# OBD-UART-ng.net
KiCad netlist of a schematic drawn in EAGLE
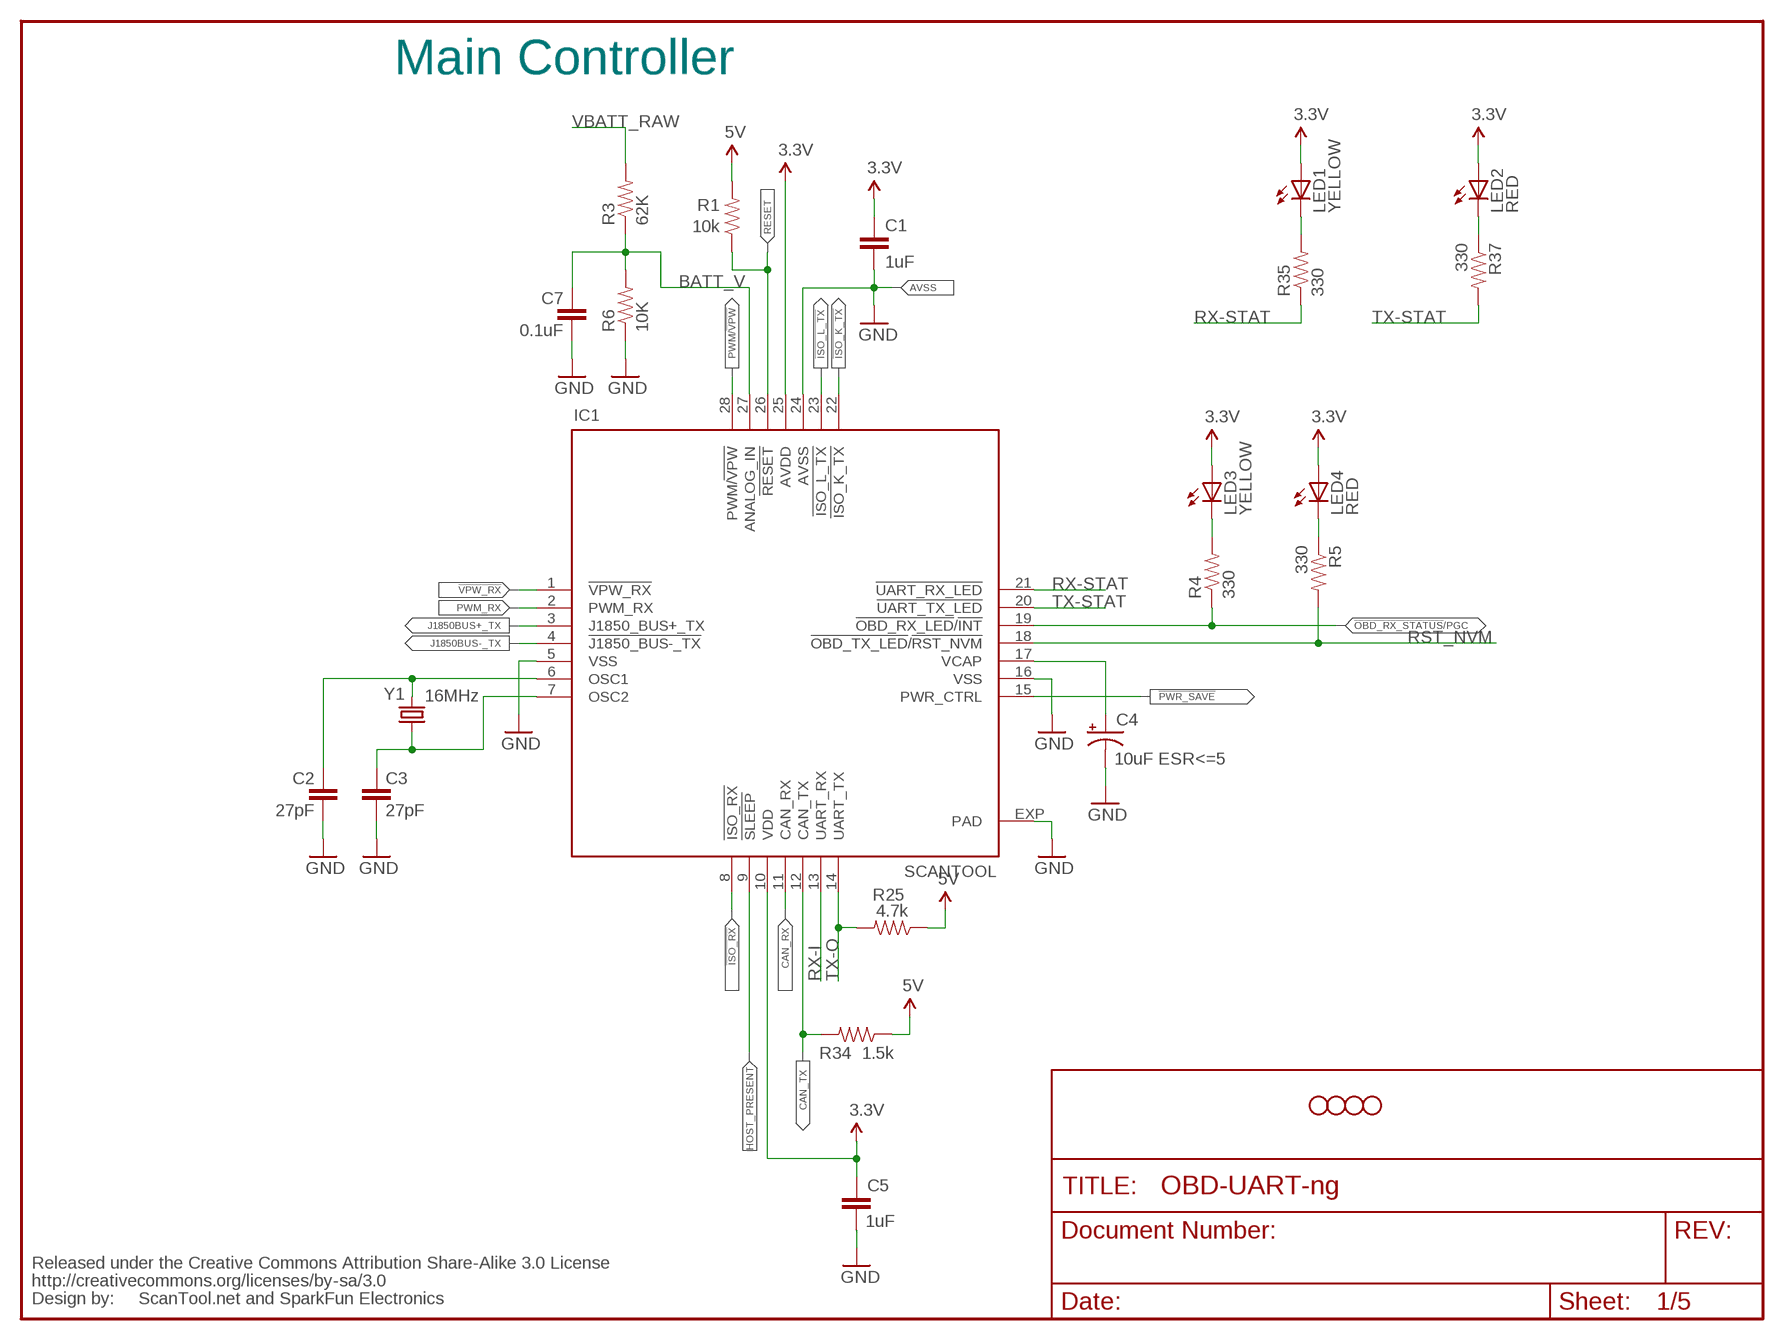
[diagram p0: schematic, sheet 1]
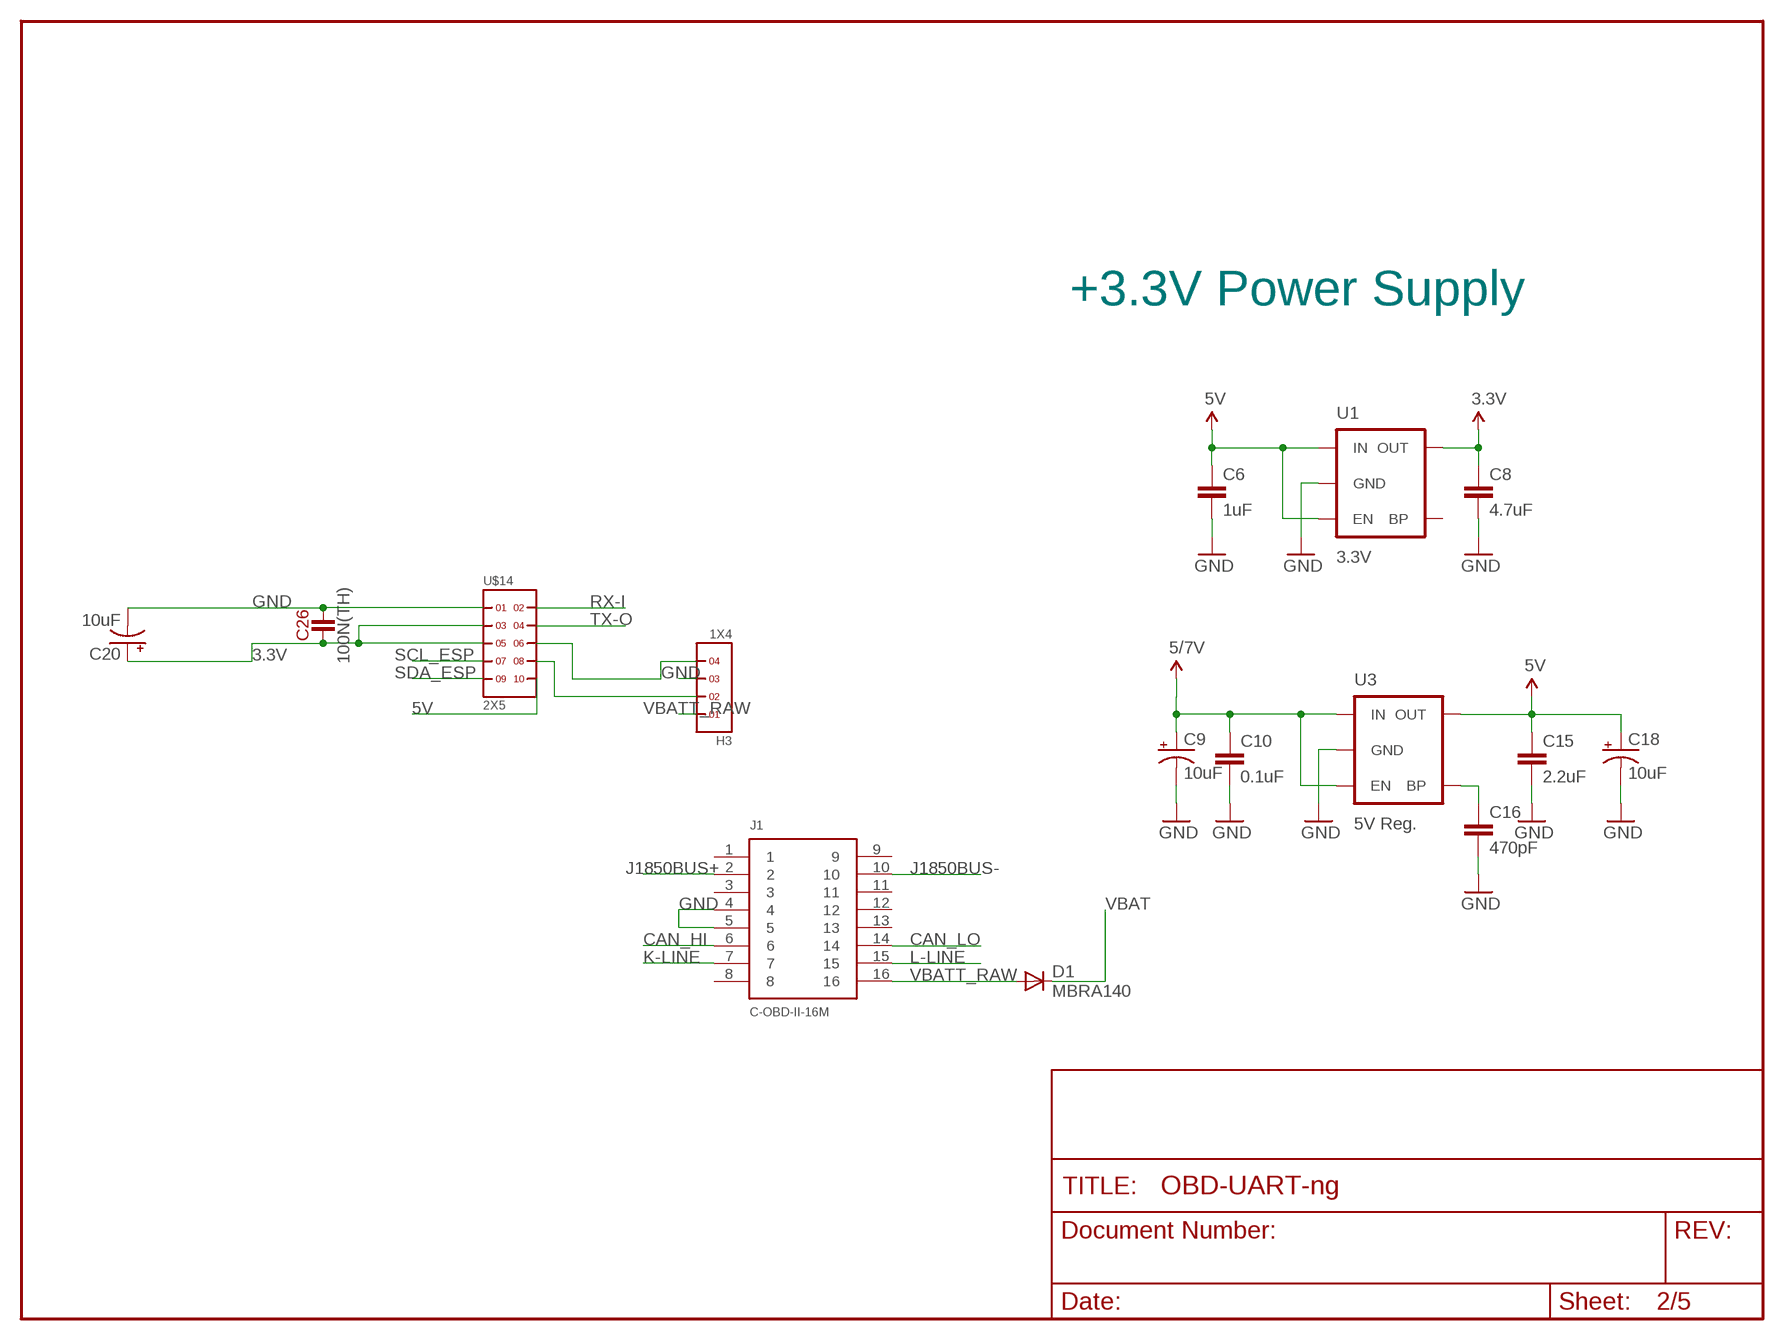
[diagram p1: schematic, sheet 2]
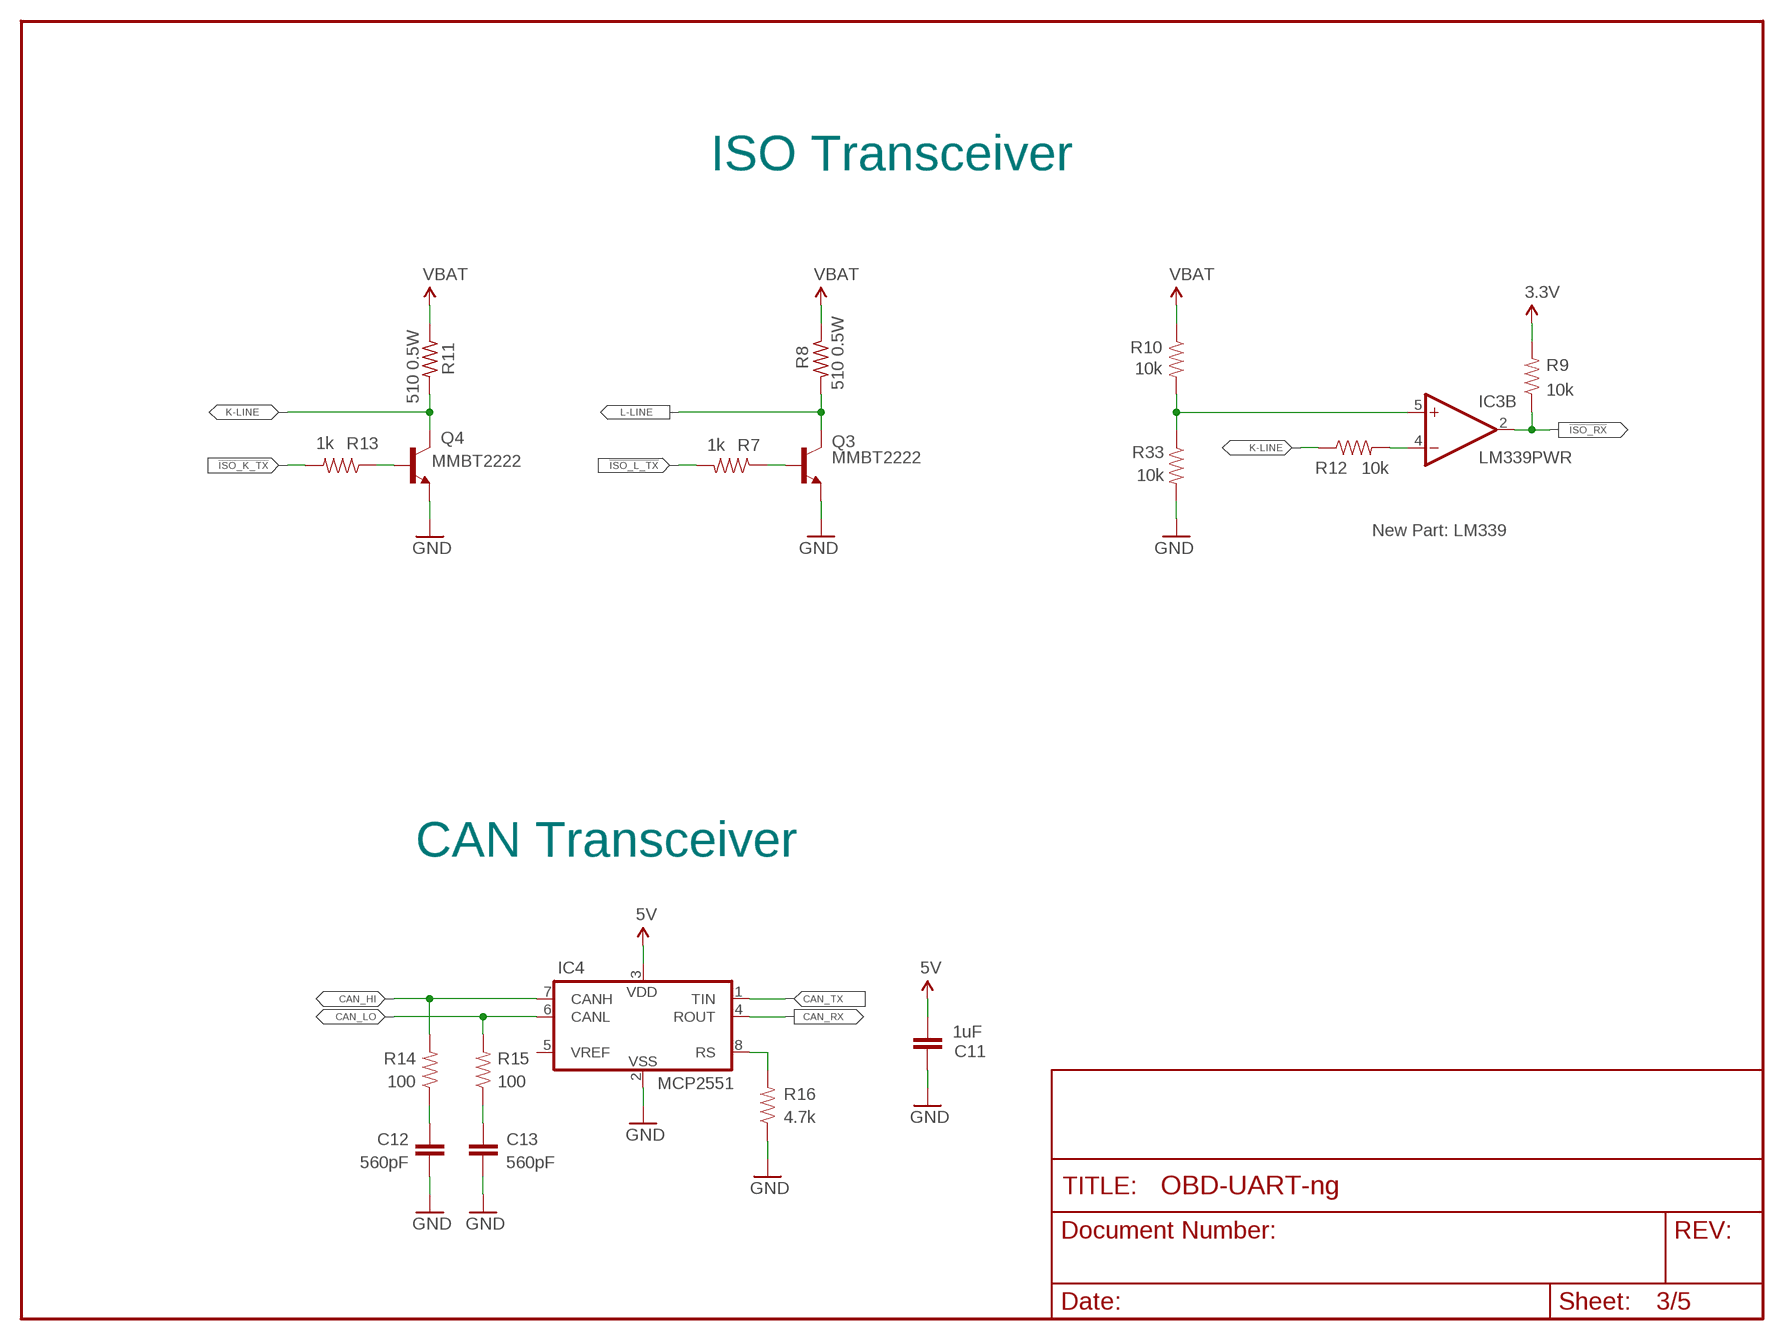
[diagram p2: schematic, sheet 3]
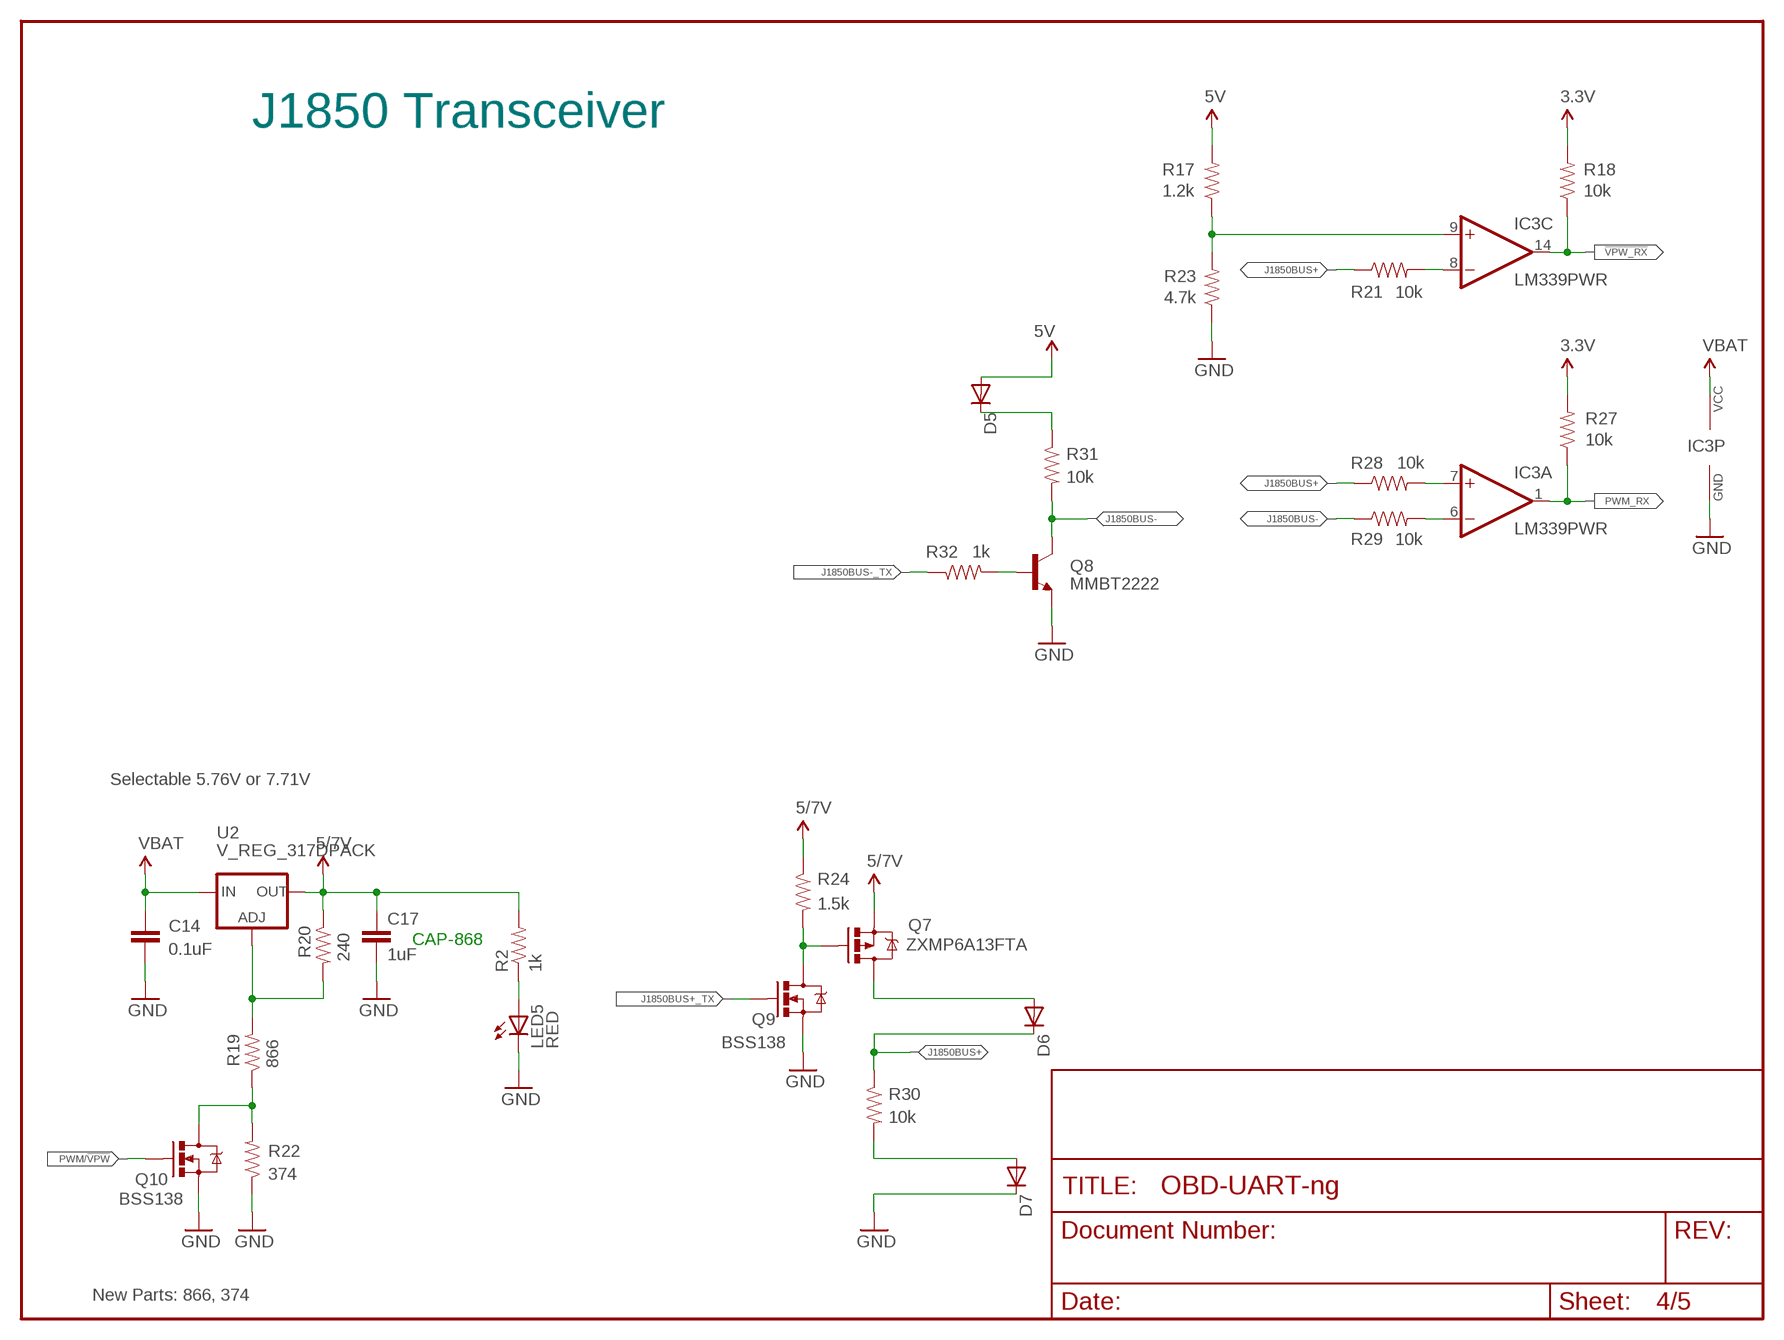
[diagram p3: schematic, sheet 4]
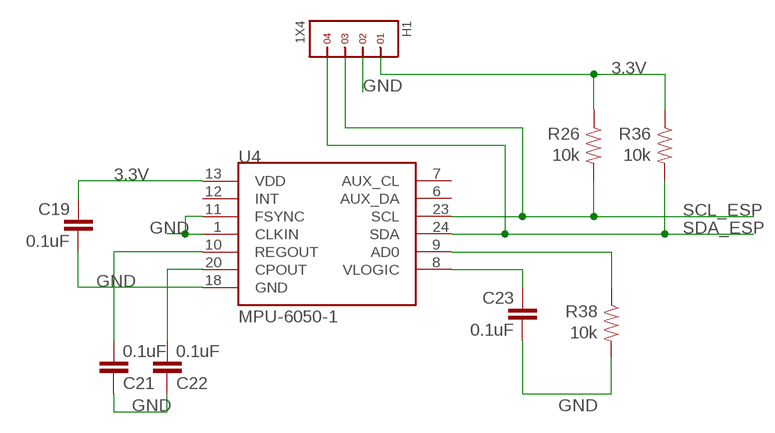
[diagram p4: schematic, sheet 5]

(export (version "E")
  (design (tool "Eeschema 10.0.6"))
  (components
    (comp (ref "C6")
      (value "1uF")
      (footprint "eagle-import:0402-CAP")
      (libsource (lib "eagle-import") (part "CAP0402-CAP"))
    )
    (comp (ref "C8")
      (value "4.7uF")
      (footprint "eagle-import:0402-CAP")
      (libsource (lib "eagle-import") (part "CAP0402-CAP"))
    )
    (comp (ref "C9")
      (value "10uF")
      (footprint "eagle-import:EIA3216")
      (libsource (lib "eagle-import") (part "CAP_POL1206"))
    )
    (comp (ref "C10")
      (value "0.1uF")
      (footprint "eagle-import:0402-CAP")
      (libsource (lib "eagle-import") (part "CAP0402-CAP"))
    )
    (comp (ref "C15")
      (value "2.2uF")
      (footprint "eagle-import:0402-CAP")
      (libsource (lib "eagle-import") (part "CAP0402-CAP"))
    )
    (comp (ref "C16")
      (value "470pF")
      (footprint "eagle-import:0402-CAP")
      (libsource (lib "eagle-import") (part "CAP0402-CAP"))
    )
    (comp (ref "C18")
      (value "10uF")
      (footprint "eagle-import:EIA3216")
      (libsource (lib "eagle-import") (part "CAP_POL1206"))
    )
    (comp (ref "C20")
      (value "10uF")
      (footprint "eagle-import:EIA3216")
      (libsource (lib "eagle-import") (part "CAP_POL1206"))
    )
    (comp (ref "C26")
      (value "100N(TH)")
      (footprint "eagle-import:C050-024X044")
      (libsource (lib "eagle-import") (part "?100N(TH)"))
    )
    (comp (ref "D1")
      (value "MBRA140")
      (footprint "eagle-import:SMA-DIODE")
      (libsource (lib "eagle-import") (part "DIODESMA"))
    )
    (comp (ref "H3")
      (value "1X4")
      (footprint "eagle-import:1X4")
      (libsource (lib "eagle-import") (part "1X4"))
    )
    (comp (ref "J1")
      (value "C-OBD-II-16M")
      (footprint "eagle-import:COMTECH_C-OBD-II-16M")
      (fields (field (name "MF") "Comtech Electronic Co., LTD"))
      (libsource (lib "eagle-import") (part "C-OBD-II-16M"))
    )
    (comp (ref "U$14")
      (value "2X5")
      (footprint "eagle-import:2X5")
      (libsource (lib "eagle-import") (part "2X5"))
    )
    (comp (ref "U1")
      (value "3.3V")
      (footprint "eagle-import:SOT23-5")
      (libsource (lib "eagle-import") (part "V_REG_LDOSMD"))
    )
    (comp (ref "U3")
      (value "5V Reg.")
      (footprint "eagle-import:SOT23-5")
      (libsource (lib "eagle-import") (part "V_REG_LDOSMD"))
    )
    (comp (ref "C11")
      (value "1uF")
      (footprint "eagle-import:0402-CAP")
      (libsource (lib "eagle-import") (part "CAP0402-CAP"))
    )
    (comp (ref "C12")
      (value "560pF")
      (footprint "eagle-import:0402-CAP")
      (libsource (lib "eagle-import") (part "CAP0402-CAP"))
    )
    (comp (ref "C13")
      (value "560pF")
      (footprint "eagle-import:0402-CAP")
      (libsource (lib "eagle-import") (part "CAP0402-CAP"))
    )
    (comp (ref "IC3")
      (value "LM339PWR")
      (footprint "eagle-import:TSSOP-14")
      (libsource (lib "eagle-import") (part "LM339PWR"))
    )
    (comp (ref "IC4")
      (value "MCP2551")
      (footprint "eagle-import:SO-8")
      (fields (field (name "PARTNUM") "MCP2551-I/SN"))
      (libsource (lib "eagle-import") (part "MCP2551-I/SN"))
    )
    (comp (ref "Q3")
      (value "MMBT2222")
      (footprint "eagle-import:SOT23-3")
      (libsource (lib "eagle-import") (part "TRANSISTOR_NPNSOT23-3"))
    )
    (comp (ref "Q4")
      (value "MMBT2222")
      (footprint "eagle-import:SOT23-3")
      (libsource (lib "eagle-import") (part "TRANSISTOR_NPNSOT23-3"))
    )
    (comp (ref "R7")
      (value "1k")
      (footprint "eagle-import:0402-RES")
      (libsource (lib "eagle-import") (part "RESISTOR0402-RES"))
    )
    (comp (ref "R8")
      (value "510 0.5W")
      (footprint "eagle-import:2010")
      (libsource (lib "eagle-import") (part "R-US_2010"))
    )
    (comp (ref "R9")
      (value "10k")
      (footprint "eagle-import:0402-RES")
      (libsource (lib "eagle-import") (part "RESISTOR0402-RES"))
    )
    (comp (ref "R10")
      (value "10k")
      (footprint "eagle-import:0402-RES")
      (libsource (lib "eagle-import") (part "RESISTOR0402-RES"))
    )
    (comp (ref "R11")
      (value "510 0.5W")
      (footprint "eagle-import:2010")
      (libsource (lib "eagle-import") (part "R-US_2010"))
    )
    (comp (ref "R12")
      (value "10k")
      (footprint "eagle-import:0402-RES")
      (libsource (lib "eagle-import") (part "RESISTOR0402-RES"))
    )
    (comp (ref "R13")
      (value "1k")
      (footprint "eagle-import:0402-RES")
      (libsource (lib "eagle-import") (part "RESISTOR0402-RES"))
    )
    (comp (ref "R14")
      (value "100")
      (footprint "eagle-import:0402-RES")
      (libsource (lib "eagle-import") (part "RESISTOR0402-RES"))
    )
    (comp (ref "R15")
      (value "100")
      (footprint "eagle-import:0402-RES")
      (libsource (lib "eagle-import") (part "RESISTOR0402-RES"))
    )
    (comp (ref "R16")
      (value "4.7k")
      (footprint "eagle-import:0402-RES")
      (libsource (lib "eagle-import") (part "RESISTOR0402-RES"))
    )
    (comp (ref "R33")
      (value "10k")
      (footprint "eagle-import:0402-RES")
      (libsource (lib "eagle-import") (part "RESISTOR0402-RES"))
    )
    (comp (ref "C19")
      (value "0.1uF")
      (footprint "eagle-import:0402-CAP")
      (libsource (lib "eagle-import") (part "CAP0402-CAP"))
    )
    (comp (ref "C21")
      (value "0.1uF")
      (footprint "eagle-import:0402-CAP")
      (libsource (lib "eagle-import") (part "CAP0402-CAP"))
    )
    (comp (ref "C22")
      (value "0.1uF")
      (footprint "eagle-import:0402-CAP")
      (libsource (lib "eagle-import") (part "CAP0402-CAP"))
    )
    (comp (ref "C23")
      (value "0.1uF")
      (footprint "eagle-import:0402-CAP")
      (libsource (lib "eagle-import") (part "CAP0402-CAP"))
    )
    (comp (ref "H1")
      (value "1X4")
      (footprint "eagle-import:1X4")
      (libsource (lib "eagle-import") (part "1X4"))
    )
    (comp (ref "R26")
      (value "10k")
      (footprint "eagle-import:0402-RES")
      (libsource (lib "eagle-import") (part "RESISTOR0402-RES"))
    )
    (comp (ref "R36")
      (value "10k")
      (footprint "eagle-import:0402-RES")
      (libsource (lib "eagle-import") (part "RESISTOR0402-RES"))
    )
    (comp (ref "R38")
      (value "10k")
      (footprint "eagle-import:0402-RES")
      (libsource (lib "eagle-import") (part "RESISTOR0402-RES"))
    )
    (comp (ref "U4")
      (value "MPU-6050-1")
      (footprint "eagle-import:QFN-24-4MM2")
      (libsource (lib "eagle-import") (part "MPU-6050-1"))
    )
    (comp (ref "C1")
      (value "1uF")
      (footprint "eagle-import:0402-CAP")
      (libsource (lib "eagle-import") (part "CAP0402-CAP"))
    )
    (comp (ref "C2")
      (value "27pF")
      (footprint "eagle-import:0402-CAP")
      (libsource (lib "eagle-import") (part "CAP0402-CAP"))
    )
    (comp (ref "C3")
      (value "27pF")
      (footprint "eagle-import:0402-CAP")
      (libsource (lib "eagle-import") (part "CAP0402-CAP"))
    )
    (comp (ref "C4")
      (value "10uF ESR<=5")
      (footprint "eagle-import:EIA3216")
      (libsource (lib "eagle-import") (part "CAP_POL1206"))
    )
    (comp (ref "C5")
      (value "1uF")
      (footprint "eagle-import:0402-CAP")
      (libsource (lib "eagle-import") (part "CAP0402-CAP"))
    )
    (comp (ref "C7")
      (value "0.1uF")
      (footprint "eagle-import:0402-CAP")
      (libsource (lib "eagle-import") (part "CAP0402-CAP"))
    )
    (comp (ref "IC1")
      (value "SCANTOOL")
      (footprint "eagle-import:_STN_SCANTOOL_QFN-28-S")
      (libsource (lib "eagle-import") (part "SCANTOOL"))
    )
    (comp (ref "JP4")
      (value "STAND-OFF")
      (footprint "eagle-import:STAND-OFF")
      (libsource (lib "eagle-import") (part "STAND-OFF"))
    )
    (comp (ref "JP5")
      (value "STAND-OFF")
      (footprint "eagle-import:STAND-OFF")
      (libsource (lib "eagle-import") (part "STAND-OFF"))
    )
    (comp (ref "JP6")
      (value "STAND-OFF")
      (footprint "eagle-import:STAND-OFF")
      (libsource (lib "eagle-import") (part "STAND-OFF"))
    )
    (comp (ref "JP7")
      (value "STAND-OFF")
      (footprint "eagle-import:STAND-OFF")
      (libsource (lib "eagle-import") (part "STAND-OFF"))
    )
    (comp (ref "LED1")
      (value "YELLOW")
      (footprint "eagle-import:LED-0603")
      (libsource (lib "eagle-import") (part "LED0603"))
    )
    (comp (ref "LED2")
      (value "RED")
      (footprint "eagle-import:LED-0603")
      (libsource (lib "eagle-import") (part "LED0603"))
    )
    (comp (ref "LED3")
      (value "YELLOW")
      (footprint "eagle-import:LED-0603")
      (libsource (lib "eagle-import") (part "LED0603"))
    )
    (comp (ref "LED4")
      (value "RED")
      (footprint "eagle-import:LED-0603")
      (libsource (lib "eagle-import") (part "LED0603"))
    )
    (comp (ref "R1")
      (value "10k")
      (footprint "eagle-import:0402-RES")
      (libsource (lib "eagle-import") (part "RESISTOR0402-RES"))
    )
    (comp (ref "R3")
      (value "62K")
      (footprint "eagle-import:0402-RES")
      (libsource (lib "eagle-import") (part "RESISTOR0402-RES"))
    )
    (comp (ref "R4")
      (value "330")
      (footprint "eagle-import:0402-RES")
      (libsource (lib "eagle-import") (part "RESISTOR0402-RES"))
    )
    (comp (ref "R5")
      (value "330")
      (footprint "eagle-import:0402-RES")
      (libsource (lib "eagle-import") (part "RESISTOR0402-RES"))
    )
    (comp (ref "R6")
      (value "10K")
      (footprint "eagle-import:0402-RES")
      (libsource (lib "eagle-import") (part "RESISTOR0402-RES"))
    )
    (comp (ref "R25")
      (value "4.7k")
      (footprint "eagle-import:0402-RES")
      (libsource (lib "eagle-import") (part "RESISTOR0402-RES"))
    )
    (comp (ref "R34")
      (value "1.5k")
      (footprint "eagle-import:0402-RES")
      (libsource (lib "eagle-import") (part "RESISTOR0402-RES"))
    )
    (comp (ref "R35")
      (value "330")
      (footprint "eagle-import:0402-RES")
      (libsource (lib "eagle-import") (part "RESISTOR0402-RES"))
    )
    (comp (ref "R37")
      (value "330")
      (footprint "eagle-import:0402-RES")
      (libsource (lib "eagle-import") (part "RESISTOR0402-RES"))
    )
    (comp (ref "U$1")
      (value "CREATIVE_COMMONS")
      (footprint "eagle-import:CREATIVE_COMMONS")
      (libsource (lib "eagle-import") (part "CREATIVE_COMMONS"))
    )
    (comp (ref "Y1")
      (value "16MHz")
      (footprint "eagle-import:CRYSTAL-SMD-5X3")
      (libsource (lib "eagle-import") (part "CRYSTAL5X3"))
    )
    (comp (ref "C14")
      (value "0.1uF")
      (footprint "eagle-import:0402-CAP")
      (libsource (lib "eagle-import") (part "CAP0402-CAP"))
    )
    (comp (ref "C17")
      (value "1uF")
      (footprint "eagle-import:0402-CAP")
      (libsource (lib "eagle-import") (part "CAP0402-CAP"))
    )
    (comp (ref "D5")
      (value "DIODESOT23")
      (footprint "eagle-import:SOT23-3")
      (libsource (lib "eagle-import") (part "DIODESOT23"))
    )
    (comp (ref "D6")
      (value "DIODESOT23")
      (footprint "eagle-import:SOT23-3")
      (libsource (lib "eagle-import") (part "DIODESOT23"))
    )
    (comp (ref "D7")
      (value "DIODESOT23")
      (footprint "eagle-import:SOT23-3")
      (libsource (lib "eagle-import") (part "DIODESOT23"))
    )
    (comp (ref "LED5")
      (value "RED")
      (footprint "eagle-import:LED-0603")
      (libsource (lib "eagle-import") (part "LED0603"))
    )
    (comp (ref "Q7")
      (value "ZXMP6A13FTA")
      (footprint "eagle-import:SOT23")
      (libsource (lib "eagle-import") (part "MOSFET-PCHANNEL"))
    )
    (comp (ref "Q8")
      (value "MMBT2222")
      (footprint "eagle-import:SOT23-3")
      (libsource (lib "eagle-import") (part "TRANSISTOR_NPNSOT23-3"))
    )
    (comp (ref "Q9")
      (value "BSS138")
      (footprint "eagle-import:SOT23-3")
      (libsource (lib "eagle-import") (part "MOSFET-NCHANNELSMD"))
    )
    (comp (ref "Q10")
      (value "BSS138")
      (footprint "eagle-import:SOT23-3")
      (libsource (lib "eagle-import") (part "MOSFET-NCHANNELSMD"))
    )
    (comp (ref "R2")
      (value "1k")
      (footprint "eagle-import:0402-RES")
      (libsource (lib "eagle-import") (part "RESISTOR0402-RES"))
    )
    (comp (ref "R17")
      (value "1.2k")
      (footprint "eagle-import:0402-RES")
      (libsource (lib "eagle-import") (part "RESISTOR0402-RES"))
    )
    (comp (ref "R18")
      (value "10k")
      (footprint "eagle-import:0402-RES")
      (libsource (lib "eagle-import") (part "RESISTOR0402-RES"))
    )
    (comp (ref "R19")
      (value "866")
      (footprint "eagle-import:0402-RES")
      (libsource (lib "eagle-import") (part "RESISTOR0402-RES"))
    )
    (comp (ref "R20")
      (value "240")
      (footprint "eagle-import:0402-RES")
      (libsource (lib "eagle-import") (part "RESISTOR0402-RES"))
    )
    (comp (ref "R21")
      (value "10k")
      (footprint "eagle-import:0402-RES")
      (libsource (lib "eagle-import") (part "RESISTOR0402-RES"))
    )
    (comp (ref "R22")
      (value "374")
      (footprint "eagle-import:0402-RES")
      (libsource (lib "eagle-import") (part "RESISTOR0402-RES"))
    )
    (comp (ref "R23")
      (value "4.7k")
      (footprint "eagle-import:0402-RES")
      (libsource (lib "eagle-import") (part "RESISTOR0402-RES"))
    )
    (comp (ref "R24")
      (value "1.5k")
      (footprint "eagle-import:0402-RES")
      (libsource (lib "eagle-import") (part "RESISTOR0402-RES"))
    )
    (comp (ref "R27")
      (value "10k")
      (footprint "eagle-import:0402-RES")
      (libsource (lib "eagle-import") (part "RESISTOR0402-RES"))
    )
    (comp (ref "R28")
      (value "10k")
      (footprint "eagle-import:0402-RES")
      (libsource (lib "eagle-import") (part "RESISTOR0402-RES"))
    )
    (comp (ref "R29")
      (value "10k")
      (footprint "eagle-import:0402-RES")
      (libsource (lib "eagle-import") (part "RESISTOR0402-RES"))
    )
    (comp (ref "R30")
      (value "10k")
      (footprint "eagle-import:0402-RES")
      (libsource (lib "eagle-import") (part "RESISTOR0402-RES"))
    )
    (comp (ref "R31")
      (value "10k")
      (footprint "eagle-import:0402-RES")
      (libsource (lib "eagle-import") (part "RESISTOR0402-RES"))
    )
    (comp (ref "R32")
      (value "1k")
      (footprint "eagle-import:0402-RES")
      (libsource (lib "eagle-import") (part "RESISTOR0402-RES"))
    )
    (comp (ref "U2")
      (value "V_REG_317DPACK")
      (footprint "eagle-import:V-REG_DPACK")
      (libsource (lib "eagle-import") (part "V_REG_317DPACK"))
    )
  )
  (nets
    (net (code "1") (name "3.3V") (class "Default")
      (node (ref "C1") (pin "1") (pinfunction "1_1") (pintype "passive"))
      (node (ref "C19") (pin "1") (pinfunction "1_1") (pintype "passive"))
      (node (ref "C20") (pin "A") (pinfunction "+_A") (pintype "passive"))
      (node (ref "C26") (pin "1") (pinfunction "1_1") (pintype "passive"))
      (node (ref "C5") (pin "1") (pinfunction "1_1") (pintype "passive"))
      (node (ref "C8") (pin "1") (pinfunction "1_1") (pintype "passive"))
      (node (ref "H1") (pin "1") (pinfunction "1_1") (pintype "bidirectional"))
      (node (ref "IC1") (pin "10") (pinfunction "VDD_10") (pintype "power_in"))
      (node (ref "IC1") (pin "25") (pinfunction "AVDD_25") (pintype "power_in"))
      (node (ref "LED1") (pin "A") (pinfunction "A_A") (pintype "passive"))
      (node (ref "LED2") (pin "A") (pinfunction "A_A") (pintype "passive"))
      (node (ref "LED3") (pin "A") (pinfunction "A_A") (pintype "passive"))
      (node (ref "LED4") (pin "A") (pinfunction "A_A") (pintype "passive"))
      (node (ref "R18") (pin "2") (pinfunction "2_2") (pintype "passive"))
      (node (ref "R26") (pin "1") (pinfunction "1_1") (pintype "passive"))
      (node (ref "R27") (pin "2") (pinfunction "2_2") (pintype "passive"))
      (node (ref "R36") (pin "1") (pinfunction "1_1") (pintype "passive"))
      (node (ref "R9") (pin "2") (pinfunction "2_2") (pintype "passive"))
      (node (ref "U$14") (pin "3") (pinfunction "3_3") (pintype "bidirectional"))
      (node (ref "U$14") (pin "5") (pinfunction "5_5") (pintype "bidirectional"))
      (node (ref "U1") (pin "5") (pinfunction "OUT_5") (pintype "passive"))
      (node (ref "U4") (pin "13") (pinfunction "VDD_13") (pintype "bidirectional"))
    )
    (net (code "2") (name "5V") (class "Default")
      (node (ref "C11") (pin "1") (pinfunction "1_1") (pintype "passive"))
      (node (ref "C15") (pin "1") (pinfunction "1_1") (pintype "passive"))
      (node (ref "C18") (pin "A") (pinfunction "+_A") (pintype "passive"))
      (node (ref "C6") (pin "1") (pinfunction "1_1") (pintype "passive"))
      (node (ref "D5") (pin "1") (pinfunction "A_1") (pintype "passive"))
      (node (ref "IC4") (pin "3") (pinfunction "VDD_3") (pintype "power_in"))
      (node (ref "R1") (pin "2") (pinfunction "2_2") (pintype "passive"))
      (node (ref "R17") (pin "2") (pinfunction "2_2") (pintype "passive"))
      (node (ref "R25") (pin "1") (pinfunction "1_1") (pintype "passive"))
      (node (ref "R34") (pin "1") (pinfunction "1_1") (pintype "passive"))
      (node (ref "U$14") (pin "10") (pinfunction "10_10") (pintype "bidirectional"))
      (node (ref "U1") (pin "1") (pinfunction "IN_1") (pintype "input"))
      (node (ref "U1") (pin "3") (pinfunction "EN_3") (pintype "input"))
      (node (ref "U3") (pin "5") (pinfunction "OUT_5") (pintype "passive"))
    )
    (net (code "3") (name "BATT_V") (class "Default")
      (node (ref "C7") (pin "1") (pinfunction "1_1") (pintype "passive"))
      (node (ref "IC1") (pin "27") (pinfunction "ANALOG_IN_27") (pintype "input"))
      (node (ref "R3") (pin "1") (pinfunction "1_1") (pintype "passive"))
      (node (ref "R6") (pin "2") (pinfunction "2_2") (pintype "passive"))
    )
    (net (code "4") (name "CAN_HI") (class "Default")
      (node (ref "IC4") (pin "7") (pinfunction "CANH_7") (pintype "bidirectional"))
      (node (ref "J1") (pin "6") (pinfunction "6_6") (pintype "passive"))
      (node (ref "R14") (pin "2") (pinfunction "2_2") (pintype "passive"))
    )
    (net (code "5") (name "CAN_LO") (class "Default")
      (node (ref "IC4") (pin "6") (pinfunction "CANL_6") (pintype "bidirectional"))
      (node (ref "J1") (pin "14") (pinfunction "14_14") (pintype "passive"))
      (node (ref "R15") (pin "2") (pinfunction "2_2") (pintype "passive"))
    )
    (net (code "6") (name "CAN_RX") (class "Default")
      (node (ref "IC1") (pin "11") (pinfunction "CAN_RX_11") (pintype "input"))
      (node (ref "IC4") (pin "4") (pinfunction "ROUT_4") (pintype "output"))
    )
    (net (code "7") (name "CAN_TX") (class "Default")
      (node (ref "IC1") (pin "12") (pinfunction "CAN_TX_12") (pintype "output"))
      (node (ref "IC4") (pin "1") (pinfunction "TIN_1") (pintype "input"))
      (node (ref "R34") (pin "2") (pinfunction "2_2") (pintype "passive"))
    )
    (net (code "8") (name "GND") (class "Default")
      (node (ref "C1") (pin "2") (pinfunction "2_2") (pintype "passive"))
      (node (ref "C10") (pin "2") (pinfunction "2_2") (pintype "passive"))
      (node (ref "C11") (pin "2") (pinfunction "2_2") (pintype "passive"))
      (node (ref "C12") (pin "2") (pinfunction "2_2") (pintype "passive"))
      (node (ref "C13") (pin "2") (pinfunction "2_2") (pintype "passive"))
      (node (ref "C14") (pin "2") (pinfunction "2_2") (pintype "passive"))
      (node (ref "C15") (pin "2") (pinfunction "2_2") (pintype "passive"))
      (node (ref "C16") (pin "2") (pinfunction "2_2") (pintype "passive"))
      (node (ref "C17") (pin "2") (pinfunction "2_2") (pintype "passive"))
      (node (ref "C18") (pin "C") (pinfunction "-_C") (pintype "passive"))
      (node (ref "C19") (pin "2") (pinfunction "2_2") (pintype "passive"))
      (node (ref "C2") (pin "2") (pinfunction "2_2") (pintype "passive"))
      (node (ref "C20") (pin "C") (pinfunction "-_C") (pintype "passive"))
      (node (ref "C21") (pin "1") (pinfunction "1_1") (pintype "passive"))
      (node (ref "C22") (pin "1") (pinfunction "1_1") (pintype "passive"))
      (node (ref "C23") (pin "2") (pinfunction "2_2") (pintype "passive"))
      (node (ref "C26") (pin "2") (pinfunction "2_2") (pintype "passive"))
      (node (ref "C3") (pin "2") (pinfunction "2_2") (pintype "passive"))
      (node (ref "C4") (pin "C") (pinfunction "-_C") (pintype "passive"))
      (node (ref "C5") (pin "2") (pinfunction "2_2") (pintype "passive"))
      (node (ref "C6") (pin "2") (pinfunction "2_2") (pintype "passive"))
      (node (ref "C7") (pin "2") (pinfunction "2_2") (pintype "passive"))
      (node (ref "C8") (pin "2") (pinfunction "2_2") (pintype "passive"))
      (node (ref "C9") (pin "C") (pinfunction "-_C") (pintype "passive"))
      (node (ref "D7") (pin "3") (pinfunction "C_3") (pintype "passive"))
      (node (ref "H1") (pin "2") (pinfunction "2_2") (pintype "bidirectional"))
      (node (ref "H3") (pin "3") (pinfunction "3_3") (pintype "bidirectional"))
      (node (ref "IC1") (pin "16") (pinfunction "VSS_16") (pintype "power_in"))
      (node (ref "IC1") (pin "24") (pinfunction "AVSS_24") (pintype "power_in"))
      (node (ref "IC1") (pin "5") (pinfunction "VSS_5") (pintype "power_in"))
      (node (ref "IC1") (pin "EXP") (pinfunction "PAD_EXP") (pintype "passive"))
      (node (ref "IC3") (pin "12") (pinfunction "GND_12") (pintype "power_in"))
      (node (ref "IC4") (pin "2") (pinfunction "VSS_2") (pintype "power_in"))
      (node (ref "J1") (pin "4") (pinfunction "4_4") (pintype "passive"))
      (node (ref "J1") (pin "5") (pinfunction "5_5") (pintype "passive"))
      (node (ref "LED5") (pin "C") (pinfunction "C_C") (pintype "passive"))
      (node (ref "Q10") (pin "2") (pinfunction "S_2") (pintype "passive"))
      (node (ref "Q3") (pin "2") (pinfunction "E_2") (pintype "passive"))
      (node (ref "Q4") (pin "2") (pinfunction "E_2") (pintype "passive"))
      (node (ref "Q8") (pin "2") (pinfunction "E_2") (pintype "passive"))
      (node (ref "Q9") (pin "2") (pinfunction "S_2") (pintype "passive"))
      (node (ref "R16") (pin "1") (pinfunction "1_1") (pintype "passive"))
      (node (ref "R22") (pin "1") (pinfunction "1_1") (pintype "passive"))
      (node (ref "R23") (pin "1") (pinfunction "1_1") (pintype "passive"))
      (node (ref "R33") (pin "2") (pinfunction "2_2") (pintype "passive"))
      (node (ref "R38") (pin "2") (pinfunction "2_2") (pintype "passive"))
      (node (ref "R6") (pin "1") (pinfunction "1_1") (pintype "passive"))
      (node (ref "U$14") (pin "1") (pinfunction "1_1") (pintype "bidirectional"))
      (node (ref "U1") (pin "2") (pinfunction "GND_2") (pintype "input"))
      (node (ref "U3") (pin "2") (pinfunction "GND_2") (pintype "input"))
      (node (ref "U4") (pin "1") (pinfunction "CLKIN_1") (pintype "bidirectional"))
      (node (ref "U4") (pin "11") (pinfunction "FSYNC_11") (pintype "bidirectional"))
      (node (ref "U4") (pin "18") (pinfunction "GND_18") (pintype "bidirectional"))
    )
    (net (code "9") (name "HOST_PRESENT") (class "Default")
      (node (ref "IC1") (pin "9") (pinfunction "~{SLEEP}_9") (pintype "input"))
    )
    (net (code "10") (name "J1850BUS+") (class "Default")
      (node (ref "D6") (pin "3") (pinfunction "C_3") (pintype "passive"))
      (node (ref "J1") (pin "2") (pinfunction "2_2") (pintype "passive"))
      (node (ref "R21") (pin "1") (pinfunction "1_1") (pintype "passive"))
      (node (ref "R28") (pin "1") (pinfunction "1_1") (pintype "passive"))
      (node (ref "R30") (pin "1") (pinfunction "1_1") (pintype "passive"))
    )
    (net (code "11") (name "J1850BUS+_TX") (class "Default")
      (node (ref "IC1") (pin "3") (pinfunction "J1850_BUS+_TX_3") (pintype "output"))
      (node (ref "Q9") (pin "1") (pinfunction "G_1") (pintype "passive"))
    )
    (net (code "12") (name "J1850BUS-") (class "Default")
      (node (ref "J1") (pin "10") (pinfunction "10_10") (pintype "passive"))
      (node (ref "Q8") (pin "3") (pinfunction "C_3") (pintype "passive"))
      (node (ref "R29") (pin "1") (pinfunction "1_1") (pintype "passive"))
      (node (ref "R31") (pin "2") (pinfunction "2_2") (pintype "passive"))
    )
    (net (code "13") (name "J1850BUS-_TX") (class "Default")
      (node (ref "IC1") (pin "4") (pinfunction "~{J1850_BUS-_TX}_4") (pintype "output"))
      (node (ref "R32") (pin "1") (pinfunction "1_1") (pintype "passive"))
    )
    (net (code "14") (name "K-LINE") (class "Default")
      (node (ref "J1") (pin "7") (pinfunction "7_7") (pintype "passive"))
      (node (ref "Q4") (pin "3") (pinfunction "C_3") (pintype "passive"))
      (node (ref "R11") (pin "2") (pinfunction "2_2") (pintype "passive"))
      (node (ref "R12") (pin "1") (pinfunction "1_1") (pintype "passive"))
    )
    (net (code "15") (name "L-LINE") (class "Default")
      (node (ref "J1") (pin "15") (pinfunction "15_15") (pintype "passive"))
      (node (ref "Q3") (pin "3") (pinfunction "C_3") (pintype "passive"))
      (node (ref "R8") (pin "2") (pinfunction "2_2") (pintype "passive"))
    )
    (net (code "16") (name "Net-(C4-+)") (class "Default")
      (node (ref "C4") (pin "A") (pinfunction "+_A") (pintype "passive"))
      (node (ref "IC1") (pin "17") (pinfunction "VCAP_17") (pintype "power_in"))
    )
    (net (code "17") (name "Net-(C12-Pad1)") (class "Default")
      (node (ref "C12") (pin "1") (pinfunction "1_1") (pintype "passive"))
      (node (ref "R14") (pin "1") (pinfunction "1_1") (pintype "passive"))
    )
    (net (code "18") (name "Net-(C13-Pad1)") (class "Default")
      (node (ref "C13") (pin "1") (pinfunction "1_1") (pintype "passive"))
      (node (ref "R15") (pin "1") (pinfunction "1_1") (pintype "passive"))
    )
    (net (code "19") (name "Net-(D5-C)") (class "Default")
      (node (ref "D5") (pin "3") (pinfunction "C_3") (pintype "passive"))
      (node (ref "R31") (pin "1") (pinfunction "1_1") (pintype "passive"))
    )
    (net (code "20") (name "Net-(D6-A)") (class "Default")
      (node (ref "D6") (pin "1") (pinfunction "A_1") (pintype "passive"))
      (node (ref "Q7") (pin "3") (pinfunction "D_3") (pintype "passive"))
    )
    (net (code "21") (name "Net-(D7-A)") (class "Default")
      (node (ref "D7") (pin "1") (pinfunction "A_1") (pintype "passive"))
      (node (ref "R30") (pin "2") (pinfunction "2_2") (pintype "passive"))
    )
    (net (code "22") (name "Net-(H3-Pad2)") (class "Default")
      (node (ref "H3") (pin "2") (pinfunction "2_2") (pintype "bidirectional"))
      (node (ref "U$14") (pin "8") (pinfunction "8_8") (pintype "bidirectional"))
    )
    (net (code "23") (name "Net-(H3-Pad4)") (class "Default")
      (node (ref "H3") (pin "4") (pinfunction "4_4") (pintype "bidirectional"))
      (node (ref "U$14") (pin "6") (pinfunction "6_6") (pintype "bidirectional"))
    )
    (net (code "24") (name "Net-(IC1-OSC1)") (class "Default")
      (node (ref "C2") (pin "1") (pinfunction "1_1") (pintype "passive"))
      (node (ref "IC1") (pin "6") (pinfunction "OSC1_6") (pintype "input"))
      (node (ref "Y1") (pin "3") (pinfunction "2_3") (pintype "passive"))
    )
    (net (code "25") (name "Net-(IC1-OSC2)") (class "Default")
      (node (ref "C3") (pin "1") (pinfunction "1_1") (pintype "passive"))
      (node (ref "IC1") (pin "7") (pinfunction "OSC2_7") (pintype "output"))
      (node (ref "Y1") (pin "1") (pinfunction "1_1") (pintype "passive"))
    )
    (net (code "26") (name "Net-(IC3A-+IN)") (class "Default")
      (node (ref "IC3") (pin "7") (pinfunction "+IN_7") (pintype "input"))
      (node (ref "R28") (pin "2") (pinfunction "2_2") (pintype "passive"))
    )
    (net (code "27") (name "Net-(IC3A--IN)") (class "Default")
      (node (ref "IC3") (pin "6") (pinfunction "-IN_6") (pintype "input"))
      (node (ref "R29") (pin "2") (pinfunction "2_2") (pintype "passive"))
    )
    (net (code "28") (name "Net-(IC3B-+IN)") (class "Default")
      (node (ref "IC3") (pin "5") (pinfunction "+IN_5") (pintype "input"))
      (node (ref "R10") (pin "2") (pinfunction "2_2") (pintype "passive"))
      (node (ref "R33") (pin "1") (pinfunction "1_1") (pintype "passive"))
    )
    (net (code "29") (name "Net-(IC3B--IN)") (class "Default")
      (node (ref "IC3") (pin "4") (pinfunction "-IN_4") (pintype "input"))
      (node (ref "R12") (pin "2") (pinfunction "2_2") (pintype "passive"))
    )
    (net (code "30") (name "Net-(IC3C-+IN)") (class "Default")
      (node (ref "IC3") (pin "9") (pinfunction "+IN_9") (pintype "input"))
      (node (ref "R17") (pin "1") (pinfunction "1_1") (pintype "passive"))
      (node (ref "R23") (pin "2") (pinfunction "2_2") (pintype "passive"))
    )
    (net (code "31") (name "Net-(IC3C--IN)") (class "Default")
      (node (ref "IC3") (pin "8") (pinfunction "-IN_8") (pintype "input"))
      (node (ref "R21") (pin "2") (pinfunction "2_2") (pintype "passive"))
    )
    (net (code "32") (name "Net-(IC4-RS)") (class "Default")
      (node (ref "IC4") (pin "8") (pinfunction "RS_8") (pintype "input"))
      (node (ref "R16") (pin "2") (pinfunction "2_2") (pintype "passive"))
    )
    (net (code "33") (name "Net-(LED1-PadC)") (class "Default")
      (node (ref "LED1") (pin "C") (pinfunction "C_C") (pintype "passive"))
      (node (ref "R35") (pin "2") (pinfunction "2_2") (pintype "passive"))
    )
    (net (code "34") (name "Net-(LED2-PadC)") (class "Default")
      (node (ref "LED2") (pin "C") (pinfunction "C_C") (pintype "passive"))
      (node (ref "R37") (pin "1") (pinfunction "1_1") (pintype "passive"))
    )
    (net (code "35") (name "Net-(LED3-PadC)") (class "Default")
      (node (ref "LED3") (pin "C") (pinfunction "C_C") (pintype "passive"))
      (node (ref "R4") (pin "2") (pinfunction "2_2") (pintype "passive"))
    )
    (net (code "36") (name "Net-(LED4-PadC)") (class "Default")
      (node (ref "LED4") (pin "C") (pinfunction "C_C") (pintype "passive"))
      (node (ref "R5") (pin "1") (pinfunction "1_1") (pintype "passive"))
    )
    (net (code "37") (name "Net-(LED5-PadA)") (class "Default")
      (node (ref "LED5") (pin "A") (pinfunction "A_A") (pintype "passive"))
      (node (ref "R2") (pin "1") (pinfunction "1_1") (pintype "passive"))
    )
    (net (code "38") (name "Net-(Q3-B)") (class "Default")
      (node (ref "Q3") (pin "1") (pinfunction "B_1") (pintype "passive"))
      (node (ref "R7") (pin "1") (pinfunction "1_1") (pintype "passive"))
    )
    (net (code "39") (name "Net-(Q4-B)") (class "Default")
      (node (ref "Q4") (pin "1") (pinfunction "B_1") (pintype "passive"))
      (node (ref "R13") (pin "1") (pinfunction "1_1") (pintype "passive"))
    )
    (net (code "40") (name "Net-(Q7-G)") (class "Default")
      (node (ref "Q7") (pin "1") (pinfunction "G_1") (pintype "passive"))
      (node (ref "Q9") (pin "3") (pinfunction "D_3") (pintype "passive"))
      (node (ref "R24") (pin "2") (pinfunction "2_2") (pintype "passive"))
    )
    (net (code "41") (name "Net-(Q8-B)") (class "Default")
      (node (ref "Q8") (pin "1") (pinfunction "B_1") (pintype "passive"))
      (node (ref "R32") (pin "2") (pinfunction "2_2") (pintype "passive"))
    )
    (net (code "42") (name "Net-(Q10-D)") (class "Default")
      (node (ref "Q10") (pin "3") (pinfunction "D_3") (pintype "passive"))
      (node (ref "R19") (pin "1") (pinfunction "1_1") (pintype "passive"))
      (node (ref "R22") (pin "2") (pinfunction "2_2") (pintype "passive"))
    )
    (net (code "43") (name "Net-(U2-ADJ)") (class "Default")
      (node (ref "R19") (pin "2") (pinfunction "2_2") (pintype "passive"))
      (node (ref "R20") (pin "2") (pinfunction "2_2") (pintype "passive"))
      (node (ref "U2") (pin "1") (pinfunction "ADJ_1") (pintype "input"))
    )
    (net (code "44") (name "Net-(U3-BP)") (class "Default")
      (node (ref "C16") (pin "1") (pinfunction "1_1") (pintype "passive"))
      (node (ref "U3") (pin "4") (pinfunction "BP_4") (pintype "input"))
    )
    (net (code "45") (name "Net-(U4-AD0)") (class "Default")
      (node (ref "R38") (pin "1") (pinfunction "1_1") (pintype "passive"))
      (node (ref "U4") (pin "9") (pinfunction "AD0_9") (pintype "bidirectional"))
    )
    (net (code "46") (name "Net-(U4-CPOUT)") (class "Default")
      (node (ref "C22") (pin "2") (pinfunction "2_2") (pintype "passive"))
      (node (ref "U4") (pin "20") (pinfunction "CPOUT_20") (pintype "bidirectional"))
    )
    (net (code "47") (name "Net-(U4-REGOUT)") (class "Default")
      (node (ref "C21") (pin "2") (pinfunction "2_2") (pintype "passive"))
      (node (ref "U4") (pin "10") (pinfunction "REGOUT_10") (pintype "bidirectional"))
    )
    (net (code "48") (name "Net-(U4-VLOGIC)") (class "Default")
      (node (ref "C23") (pin "1") (pinfunction "1_1") (pintype "passive"))
      (node (ref "U4") (pin "8") (pinfunction "VLOGIC_8") (pintype "bidirectional"))
    )
    (net (code "49") (name "PWM_RX") (class "Default")
      (node (ref "IC1") (pin "2") (pinfunction "PWM_RX_2") (pintype "input"))
      (node (ref "IC3") (pin "1") (pinfunction "OUT_1") (pintype "output"))
      (node (ref "R27") (pin "1") (pinfunction "1_1") (pintype "passive"))
    )
    (net (code "50") (name "PWM{slash}~{VPW}") (class "Default")
      (node (ref "IC1") (pin "28") (pinfunction "PWM/~{VPW}_28") (pintype "output"))
      (node (ref "Q10") (pin "1") (pinfunction "G_1") (pintype "passive"))
    )
    (net (code "51") (name "RESET") (class "Default")
      (node (ref "IC1") (pin "26") (pinfunction "~{RESET}_26") (pintype "input"))
      (node (ref "R1") (pin "1") (pinfunction "1_1") (pintype "passive"))
    )
    (net (code "52") (name "RST_NVM") (class "Default")
      (node (ref "IC1") (pin "18") (pinfunction "~{OBD_TX_LED}/~{RST_NVM}_18") (pintype "bidirectional"))
      (node (ref "R5") (pin "2") (pinfunction "2_2") (pintype "passive"))
    )
    (net (code "53") (name "RX-I") (class "Default")
      (node (ref "IC1") (pin "13") (pinfunction "UART_RX_13") (pintype "input"))
      (node (ref "U$14") (pin "2") (pinfunction "2_2") (pintype "bidirectional"))
    )
    (net (code "54") (name "RX-STAT") (class "Default")
      (node (ref "IC1") (pin "21") (pinfunction "~{UART_RX_LED}_21") (pintype "output"))
      (node (ref "R35") (pin "1") (pinfunction "1_1") (pintype "passive"))
    )
    (net (code "55") (name "SCL_ESP") (class "Default")
      (node (ref "H1") (pin "3") (pinfunction "3_3") (pintype "bidirectional"))
      (node (ref "R26") (pin "2") (pinfunction "2_2") (pintype "passive"))
      (node (ref "U$14") (pin "7") (pinfunction "7_7") (pintype "bidirectional"))
      (node (ref "U4") (pin "23") (pinfunction "SCL_23") (pintype "bidirectional"))
    )
    (net (code "56") (name "SDA_ESP") (class "Default")
      (node (ref "H1") (pin "4") (pinfunction "4_4") (pintype "bidirectional"))
      (node (ref "R36") (pin "2") (pinfunction "2_2") (pintype "passive"))
      (node (ref "U$14") (pin "9") (pinfunction "9_9") (pintype "bidirectional"))
      (node (ref "U4") (pin "24") (pinfunction "SDA_24") (pintype "bidirectional"))
    )
    (net (code "57") (name "TX-O") (class "Default")
      (node (ref "IC1") (pin "14") (pinfunction "UART_TX_14") (pintype "output"))
      (node (ref "R25") (pin "2") (pinfunction "2_2") (pintype "passive"))
      (node (ref "U$14") (pin "4") (pinfunction "4_4") (pintype "bidirectional"))
    )
    (net (code "58") (name "TX-STAT") (class "Default")
      (node (ref "IC1") (pin "20") (pinfunction "~{UART_TX_LED}_20") (pintype "output"))
      (node (ref "R37") (pin "2") (pinfunction "2_2") (pintype "passive"))
    )
    (net (code "59") (name "VBAT") (class "Default")
      (node (ref "C14") (pin "1") (pinfunction "1_1") (pintype "passive"))
      (node (ref "D1") (pin "C") (pinfunction "C_C") (pintype "passive"))
      (node (ref "IC3") (pin "3") (pinfunction "VCC_3") (pintype "power_in"))
      (node (ref "R10") (pin "1") (pinfunction "1_1") (pintype "passive"))
      (node (ref "R11") (pin "1") (pinfunction "1_1") (pintype "passive"))
      (node (ref "R8") (pin "1") (pinfunction "1_1") (pintype "passive"))
      (node (ref "U2") (pin "3") (pinfunction "IN_3") (pintype "input"))
    )
    (net (code "60") (name "VBATT_RAW") (class "Default")
      (node (ref "D1") (pin "A") (pinfunction "A_A") (pintype "passive"))
      (node (ref "H3") (pin "1") (pinfunction "1_1") (pintype "bidirectional"))
      (node (ref "J1") (pin "16") (pinfunction "16_16") (pintype "passive"))
      (node (ref "R3") (pin "2") (pinfunction "2_2") (pintype "passive"))
    )
    (net (code "61") (name "VCC") (class "Default")
      (node (ref "C10") (pin "1") (pinfunction "1_1") (pintype "passive"))
      (node (ref "C17") (pin "1") (pinfunction "1_1") (pintype "passive"))
      (node (ref "C9") (pin "A") (pinfunction "+_A") (pintype "passive"))
      (node (ref "Q7") (pin "2") (pinfunction "S_2") (pintype "passive"))
      (node (ref "R2") (pin "2") (pinfunction "2_2") (pintype "passive"))
      (node (ref "R20") (pin "1") (pinfunction "1_1") (pintype "passive"))
      (node (ref "R24") (pin "1") (pinfunction "1_1") (pintype "passive"))
      (node (ref "U2") (pin "4") (pinfunction "OUT_4") (pintype "output"))
      (node (ref "U3") (pin "1") (pinfunction "IN_1") (pintype "input"))
      (node (ref "U3") (pin "3") (pinfunction "EN_3") (pintype "input"))
    )
    (net (code "62") (name "unconnected-(IC4-VREF-Pad5)") (class "Default")
      (node (ref "IC4") (pin "5") (pinfunction "VREF_5") (pintype "output"))
    )
    (net (code "63") (name "unconnected-(J1-Pad1)") (class "Default")
      (node (ref "J1") (pin "1") (pinfunction "1_1") (pintype "passive"))
    )
    (net (code "64") (name "unconnected-(J1-Pad3)") (class "Default")
      (node (ref "J1") (pin "3") (pinfunction "3_3") (pintype "passive"))
    )
    (net (code "65") (name "unconnected-(J1-Pad8)") (class "Default")
      (node (ref "J1") (pin "8") (pinfunction "8_8") (pintype "passive"))
    )
    (net (code "66") (name "unconnected-(J1-Pad9)") (class "Default")
      (node (ref "J1") (pin "9") (pinfunction "9_9") (pintype "passive"))
    )
    (net (code "67") (name "unconnected-(J1-Pad11)") (class "Default")
      (node (ref "J1") (pin "11") (pinfunction "11_11") (pintype "passive"))
    )
    (net (code "68") (name "unconnected-(J1-Pad12)") (class "Default")
      (node (ref "J1") (pin "12") (pinfunction "12_12") (pintype "passive"))
    )
    (net (code "69") (name "unconnected-(J1-Pad13)") (class "Default")
      (node (ref "J1") (pin "13") (pinfunction "13_13") (pintype "passive"))
    )
    (net (code "70") (name "unconnected-(U1-BP-Pad4)") (class "Default")
      (node (ref "U1") (pin "4") (pinfunction "BP_4") (pintype "input"))
    )
    (net (code "71") (name "unconnected-(U4-AUX_CL-Pad7)") (class "Default")
      (node (ref "U4") (pin "7") (pinfunction "AUX_CL_7") (pintype "bidirectional"))
    )
    (net (code "72") (name "unconnected-(U4-AUX_DA-Pad6)") (class "Default")
      (node (ref "U4") (pin "6") (pinfunction "AUX_DA_6") (pintype "bidirectional"))
    )
    (net (code "73") (name "unconnected-(U4-INT-Pad12)") (class "Default")
      (node (ref "U4") (pin "12") (pinfunction "INT_12") (pintype "bidirectional"))
    )
    (net (code "74") (name "~{ISO_K_TX}") (class "Default")
      (node (ref "IC1") (pin "22") (pinfunction "~{ISO_K_TX}_22") (pintype "output"))
      (node (ref "R13") (pin "2") (pinfunction "2_2") (pintype "passive"))
    )
    (net (code "75") (name "~{ISO_L_TX}") (class "Default")
      (node (ref "IC1") (pin "23") (pinfunction "~{ISO_L_TX}_23") (pintype "output"))
      (node (ref "R7") (pin "2") (pinfunction "2_2") (pintype "passive"))
    )
    (net (code "76") (name "~{ISO_RX}") (class "Default")
      (node (ref "IC1") (pin "8") (pinfunction "~{ISO_RX}_8") (pintype "input"))
      (node (ref "IC3") (pin "2") (pinfunction "OUT_2") (pintype "output"))
      (node (ref "R9") (pin "1") (pinfunction "1_1") (pintype "passive"))
    )
    (net (code "77") (name "~{OBD_RX_STATUS}{slash}PGC") (class "Default")
      (node (ref "IC1") (pin "19") (pinfunction "~{OBD_RX_LED}/~{INT}_19") (pintype "output"))
      (node (ref "R4") (pin "1") (pinfunction "1_1") (pintype "passive"))
    )
    (net (code "78") (name "~{PWR_SAVE}") (class "Default")
      (node (ref "IC1") (pin "15") (pinfunction "PWR_CTRL_15") (pintype "output"))
    )
    (net (code "79") (name "~{VPW_RX}") (class "Default")
      (node (ref "IC1") (pin "1") (pinfunction "~{VPW_RX}_1") (pintype "input"))
      (node (ref "IC3") (pin "14") (pinfunction "OUT_14") (pintype "output"))
      (node (ref "R18") (pin "1") (pinfunction "1_1") (pintype "passive"))
    )
  )
)
